# keyDuino_v5_rev1.net
KiCad netlist of a schematic drawn in EAGLE
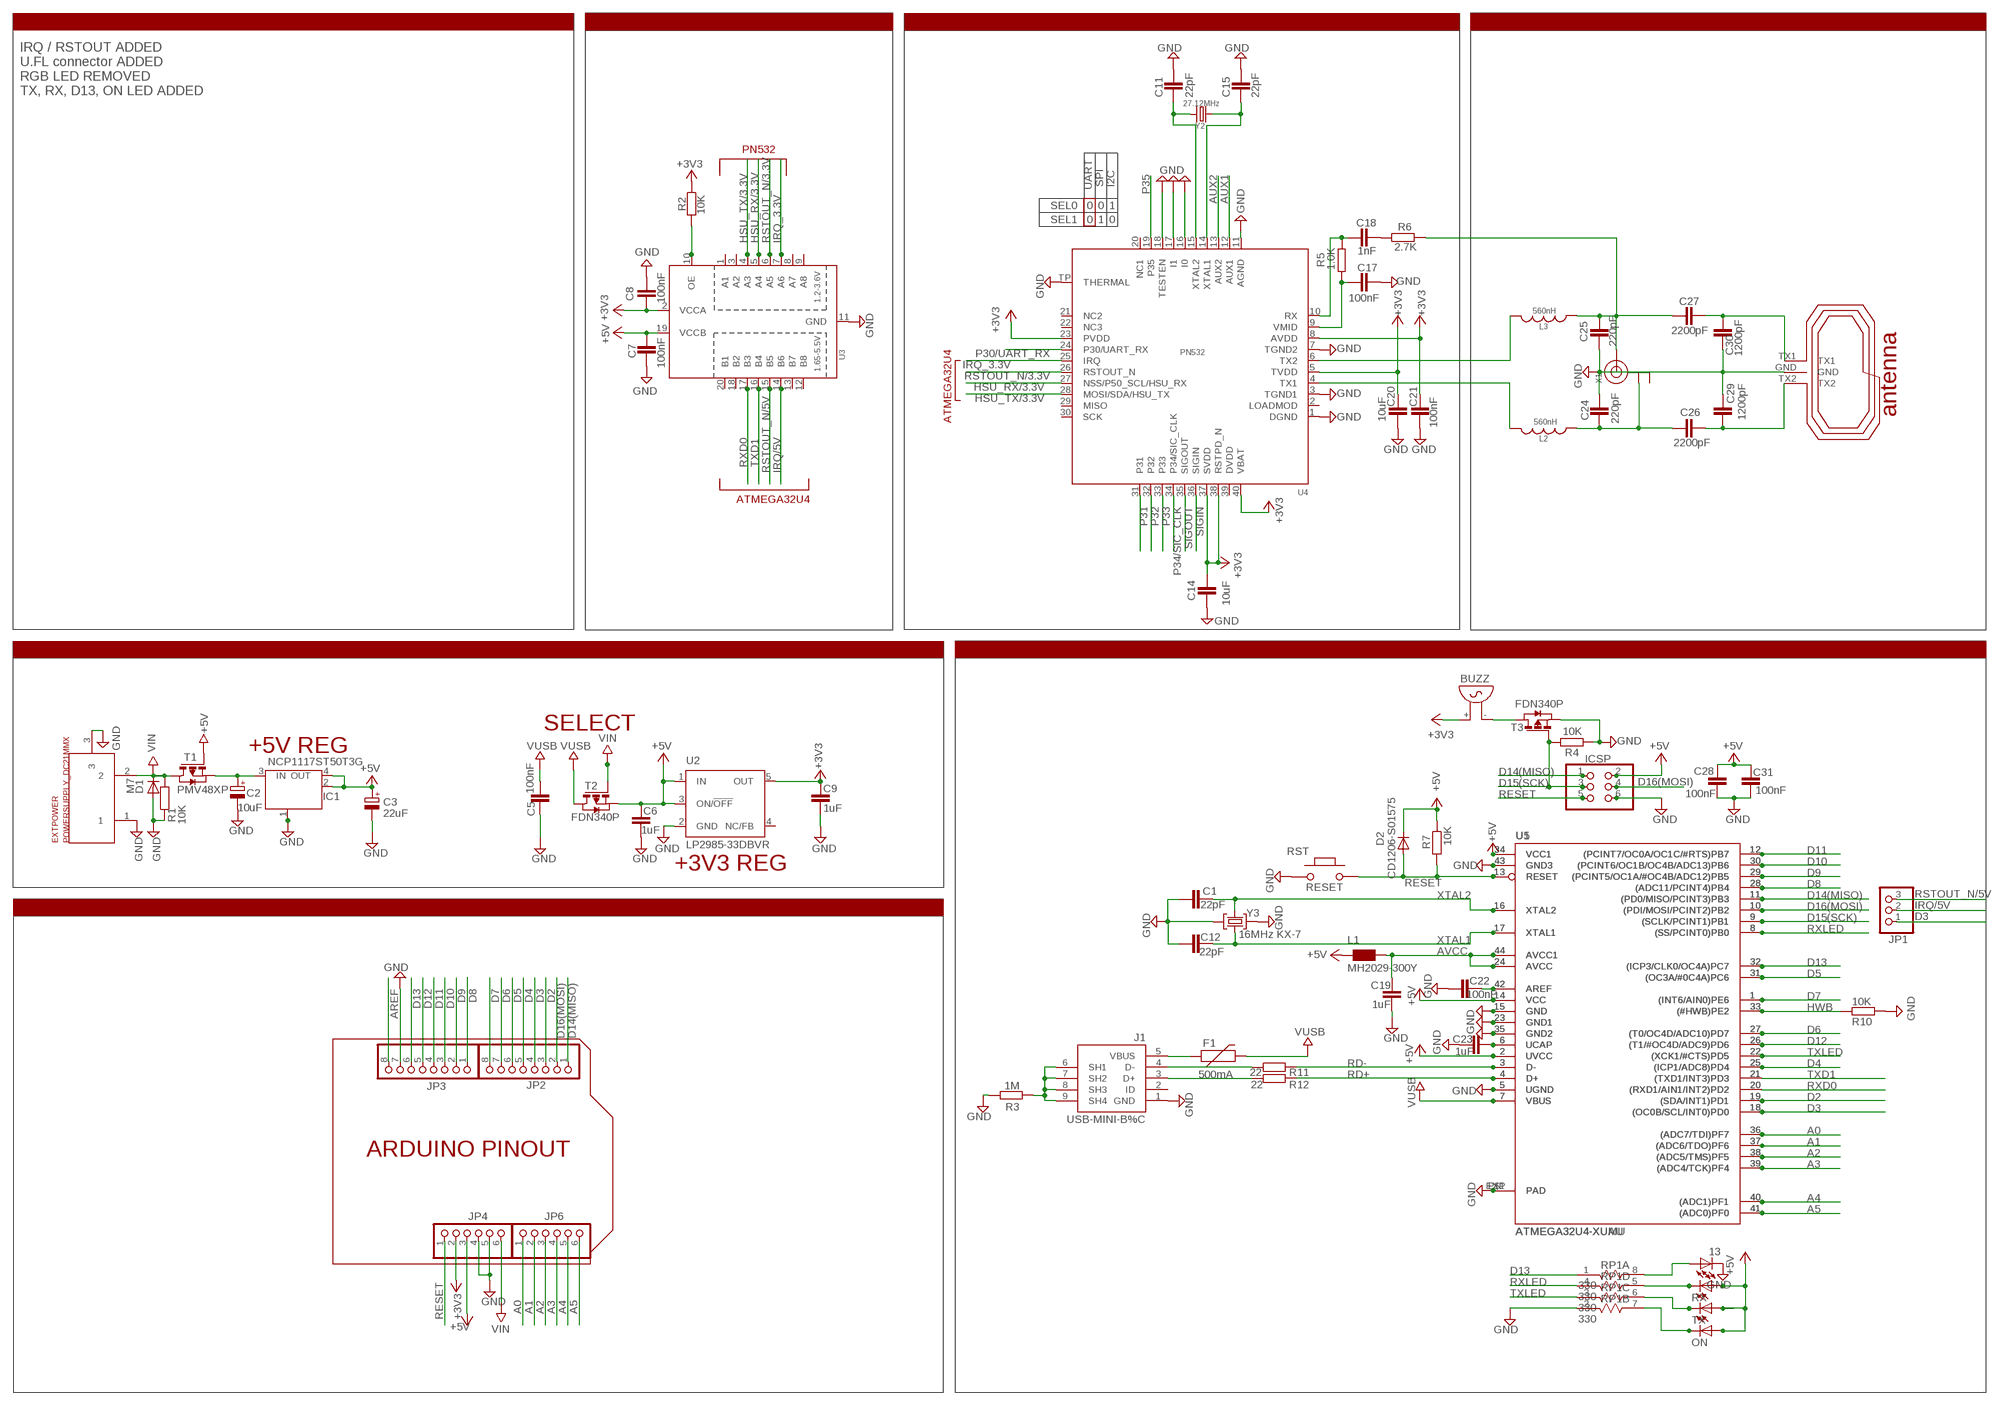
[diagram p0: schematic, sheet 1]

(export (version "E")
  (design (tool "Eeschema 10.0.6"))
  (components
    (comp (ref "13")
      (value "LEDCHIPLED_0603")
      (footprint "eagle-import:CHIPLED_0603")
      (libsource (lib "eagle-import") (part "LEDCHIPLED_0603"))
    )
    (comp (ref "BUZZ")
      (value "F/QMX")
      (footprint "eagle-import:F_QMX")
      (libsource (lib "eagle-import") (part "F/QMX"))
    )
    (comp (ref "C1")
      (value "22pF")
      (footprint "eagle-import:0603-CAP")
      (libsource (lib "eagle-import") (part "CAP0603-CAP"))
    )
    (comp (ref "C2")
      (value "10uF")
      (footprint "eagle-import:SMC_B")
      (libsource (lib "eagle-import") (part "CPOL-EUSMCB"))
    )
    (comp (ref "C3")
      (value "22uF")
      (footprint "eagle-import:SMC_B")
      (libsource (lib "eagle-import") (part "CPOL-EUSMCB"))
    )
    (comp (ref "C5")
      (value "100nF")
      (footprint "eagle-import:C0603")
      (libsource (lib "eagle-import") (part "resistor_C-EUC0603"))
    )
    (comp (ref "C6")
      (value "1uF")
      (footprint "eagle-import:C0603")
      (libsource (lib "eagle-import") (part "C-EUC0603"))
    )
    (comp (ref "C7")
      (value "100nF")
      (footprint "eagle-import:C0603")
      (libsource (lib "eagle-import") (part "C-EUC0603"))
    )
    (comp (ref "C8")
      (value "100nF")
      (footprint "eagle-import:C0603")
      (libsource (lib "eagle-import") (part "C-EUC0603"))
    )
    (comp (ref "C9")
      (value "1uF")
      (footprint "eagle-import:C0603")
      (libsource (lib "eagle-import") (part "C-EUC0603"))
    )
    (comp (ref "C11")
      (value "22pF")
      (footprint "eagle-import:0603-CAP")
      (libsource (lib "eagle-import") (part "CAP0603-CAP"))
    )
    (comp (ref "C12")
      (value "22pF")
      (footprint "eagle-import:0603-CAP")
      (libsource (lib "eagle-import") (part "CAP0603-CAP"))
    )
    (comp (ref "C14")
      (value "10uF")
      (footprint "eagle-import:C0805")
      (libsource (lib "eagle-import") (part "C-EUC0805"))
    )
    (comp (ref "C15")
      (value "22pF")
      (footprint "eagle-import:0603-CAP")
      (libsource (lib "eagle-import") (part "CAP0603-CAP"))
    )
    (comp (ref "C17")
      (value "100nF")
      (footprint "eagle-import:C0603")
      (libsource (lib "eagle-import") (part "C-EUC0603"))
    )
    (comp (ref "C18")
      (value "1nF")
      (footprint "eagle-import:C0603")
      (libsource (lib "eagle-import") (part "C-EUC0603"))
    )
    (comp (ref "C19")
      (value "1uF")
      (footprint "eagle-import:C0603")
      (libsource (lib "eagle-import") (part "resistor_C-EUC0603"))
    )
    (comp (ref "C20")
      (value "10uF")
      (footprint "eagle-import:C0805")
      (libsource (lib "eagle-import") (part "C-EUC0805"))
    )
    (comp (ref "C21")
      (value "100nF")
      (footprint "eagle-import:C0805")
      (libsource (lib "eagle-import") (part "C-EUC0805"))
    )
    (comp (ref "C22")
      (value "100nF")
      (footprint "eagle-import:C0603")
      (libsource (lib "eagle-import") (part "resistor_C-EUC0603"))
    )
    (comp (ref "C23")
      (value "1uF")
      (footprint "eagle-import:C0603")
      (libsource (lib "eagle-import") (part "resistor_C-EUC0603"))
    )
    (comp (ref "C24")
      (value "220pF")
      (footprint "eagle-import:C0603")
      (libsource (lib "eagle-import") (part "C-EUC0603"))
    )
    (comp (ref "C25")
      (value "220pF")
      (footprint "eagle-import:C0603")
      (libsource (lib "eagle-import") (part "C-EUC0603"))
    )
    (comp (ref "C26")
      (value "2200pF")
      (footprint "eagle-import:C0603")
      (libsource (lib "eagle-import") (part "C-EUC0603"))
    )
    (comp (ref "C27")
      (value "2200pF")
      (footprint "eagle-import:C0603")
      (libsource (lib "eagle-import") (part "C-EUC0603"))
    )
    (comp (ref "C28")
      (value "100nF")
      (footprint "eagle-import:C0603")
      (libsource (lib "eagle-import") (part "resistor_C-EUC0603"))
    )
    (comp (ref "C29")
      (value "1200pF")
      (footprint "eagle-import:C0603")
      (libsource (lib "eagle-import") (part "C-EUC0603"))
    )
    (comp (ref "C30")
      (value "1200pF")
      (footprint "eagle-import:C0603")
      (libsource (lib "eagle-import") (part "C-EUC0603"))
    )
    (comp (ref "C31")
      (value "100nF")
      (footprint "eagle-import:C0603")
      (libsource (lib "eagle-import") (part "resistor_C-EUC0603"))
    )
    (comp (ref "D1")
      (value "M7")
      (footprint "eagle-import:SMB")
      (libsource (lib "eagle-import") (part "DIODE-SMB"))
    )
    (comp (ref "D2")
      (value "CD1206-S01575")
      (footprint "eagle-import:MINIMELF")
      (libsource (lib "eagle-import") (part "DIODE-MINIMELF"))
    )
    (comp (ref "EXTPOWER")
      (value "POWERSUPPLY_DC21MMX")
      (footprint "eagle-import:POWERSUPPLY_DC-21MM")
      (libsource (lib "eagle-import") (part "POWERSUPPLY_DC21MMX"))
    )
    (comp (ref "F1")
      (value "500mA")
      (footprint "eagle-import:PTC-1206")
      (libsource (lib "eagle-import") (part "PTCSMD"))
    )
    (comp (ref "IC1")
      (value "NCP1117ST50T3G")
      (footprint "eagle-import:SOT223")
      (libsource (lib "eagle-import") (part "MC33269ST-3.3T3"))
    )
    (comp (ref "ICSP")
      (value "ICSP")
      (footprint "eagle-import:2X03")
      (libsource (lib "eagle-import") (part "PINHD-2X3"))
    )
    (comp (ref "J1")
      (value "USB-MINI-B%C")
      (footprint "eagle-import:USB-MINI-B_2")
      (libsource (lib "eagle-import") (part "USB-MINI-B%C"))
    )
    (comp (ref "JP1")
      (value "PINHD-1X3")
      (footprint "eagle-import:1X03")
      (libsource (lib "eagle-import") (part "PINHD-1X3"))
    )
    (comp (ref "JP2")
      (value "PINHD-1X8CLEANBIG")
      (footprint "eagle-import:1X08-CLEANBIG")
      (libsource (lib "eagle-import") (part "PINHD-1X8CLEANBIG"))
    )
    (comp (ref "JP3")
      (value "PINHD-1X8CLEANBIG")
      (footprint "eagle-import:1X08-CLEANBIG")
      (libsource (lib "eagle-import") (part "PINHD-1X8CLEANBIG"))
    )
    (comp (ref "JP4")
      (value "PINHD-1X6CB")
      (footprint "eagle-import:1X06-CLEANBIG")
      (libsource (lib "eagle-import") (part "PINHD-1X6CB"))
    )
    (comp (ref "JP6")
      (value "PINHD-1X6CB")
      (footprint "eagle-import:1X06-CLEANBIG")
      (libsource (lib "eagle-import") (part "PINHD-1X6CB"))
    )
    (comp (ref "L1")
      (value "MH2029-300Y")
      (footprint "eagle-import:0805")
      (libsource (lib "eagle-import") (part "WE-CBF_0805"))
    )
    (comp (ref "L2")
      (value "560nH")
      (footprint "eagle-import:0805@1")
      (libsource (lib "eagle-import") (part "INDUCTOR0805"))
    )
    (comp (ref "L3")
      (value "560nH")
      (footprint "eagle-import:0805@1")
      (libsource (lib "eagle-import") (part "INDUCTOR0805"))
    )
    (comp (ref "ON")
      (value "LEDCHIPLED_0603")
      (footprint "eagle-import:CHIPLED_0603")
      (libsource (lib "eagle-import") (part "LEDCHIPLED_0603"))
    )
    (comp (ref "R1")
      (value "10K")
      (footprint "eagle-import:R0603")
      (libsource (lib "eagle-import") (part "resistor_R-EU_R0603"))
    )
    (comp (ref "R2")
      (value "10K")
      (footprint "eagle-import:R0603")
      (libsource (lib "eagle-import") (part "R-EU_R0603"))
    )
    (comp (ref "R3")
      (value "1M")
      (footprint "eagle-import:R0805")
      (libsource (lib "eagle-import") (part "R-EU_R0805"))
    )
    (comp (ref "R4")
      (value "10K")
      (footprint "eagle-import:R0603")
      (libsource (lib "eagle-import") (part "R-EU_R0603"))
    )
    (comp (ref "R5")
      (value "1.0K")
      (footprint "eagle-import:R0603")
      (libsource (lib "eagle-import") (part "R-EU_R0603"))
    )
    (comp (ref "R6")
      (value "2.7K")
      (footprint "eagle-import:R0603")
      (libsource (lib "eagle-import") (part "R-EU_R0603"))
    )
    (comp (ref "R7")
      (value "10K")
      (footprint "eagle-import:R0603")
      (libsource (lib "eagle-import") (part "R-EU_R0603"))
    )
    (comp (ref "R10")
      (value "10K")
      (footprint "eagle-import:R0603")
      (libsource (lib "eagle-import") (part "R-EU_R0603"))
    )
    (comp (ref "R11")
      (value "22")
      (footprint "eagle-import:R0603")
      (libsource (lib "eagle-import") (part "R-EU_R0603"))
    )
    (comp (ref "R12")
      (value "22")
      (footprint "eagle-import:R0603")
      (libsource (lib "eagle-import") (part "R-EU_R0603"))
    )
    (comp (ref "RP1")
      (value "330")
      (footprint "eagle-import:RES4NT")
      (libsource (lib "eagle-import") (part "RES4NT"))
    )
    (comp (ref "RST")
      (value "RESET")
      (footprint "eagle-import:157SW")
      (libsource (lib "eagle-import") (part "PB157"))
    )
    (comp (ref "RX")
      (value "LEDCHIPLED_0603")
      (footprint "eagle-import:CHIPLED_0603")
      (libsource (lib "eagle-import") (part "LEDCHIPLED_0603"))
    )
    (comp (ref "T1")
      (value "PMV48XP")
      (footprint "eagle-import:SOT-23")
      (libsource (lib "eagle-import") (part "PMOSSOT23"))
    )
    (comp (ref "T2")
      (value "FDN340P")
      (footprint "eagle-import:SOT-23")
      (libsource (lib "eagle-import") (part "PMOSSOT23"))
    )
    (comp (ref "T3")
      (value "FDN340P")
      (footprint "eagle-import:SOT-23")
      (libsource (lib "eagle-import") (part "PMOSSOT23"))
    )
    (comp (ref "TX")
      (value "LEDCHIPLED_0603")
      (footprint "eagle-import:CHIPLED_0603")
      (libsource (lib "eagle-import") (part "LEDCHIPLED_0603"))
    )
    (comp (ref "U$1")
      (value "ANT_V3")
      (footprint "eagle-import:ANT_13.56_P4")
      (libsource (lib "eagle-import") (part "ANT_V3"))
    )
    (comp (ref "U1")
      (value "ATMEGA32U4-XUAU")
      (footprint "eagle-import:TQFP44-PAD")
      (libsource (lib "eagle-import") (part "ATMEGA32U4-XUAU"))
    )
    (comp (ref "U2")
      (value "LP2985-33DBVR")
      (footprint "eagle-import:SOT23-DBV")
      (libsource (lib "eagle-import") (part "LP2985-XXDBVR33"))
    )
    (comp (ref "U3")
      (value "TXB0108PWR")
      (footprint "eagle-import:TSSOP20")
      (libsource (lib "eagle-import") (part "TXB0108PWR"))
    )
    (comp (ref "U4")
      (value "PN532")
      (footprint "eagle-import:HVQFN40-6X6")
      (libsource (lib "eagle-import") (part "PN532"))
    )
    (comp (ref "U5")
      (value "ATMEGA32U4-XUMU")
      (footprint "eagle-import:QFN44ML7X7")
      (libsource (lib "eagle-import") (part "ATMEGA32U4-XUMU"))
    )
    (comp (ref "X1")
      (value "ANTENNA_U.FL")
      (footprint "eagle-import:U.FL")
      (libsource (lib "eagle-import") (part "ANTENNA_U.FL"))
    )
    (comp (ref "Y2")
      (value "27.12MHz")
      (footprint "eagle-import:CRYSTAL_3.2X2.5")
      (libsource (lib "eagle-import") (part "CRYSTALTHIN"))
    )
    (comp (ref "Y3")
      (value "16MHz KX-7")
      (footprint "eagle-import:CRYSTAL-3.2-2.5")
      (libsource (lib "eagle-import") (part "CRYSTAL-3.2-2.5"))
    )
  )
  (nets
    (net (code "1") (name "+3V3") (class "Default")
      (node (ref "BUZZ") (pin "+") (pinfunction "2_+") (pintype "passive"))
      (node (ref "C14") (pin "2") (pinfunction "2_2") (pintype "passive"))
      (node (ref "C20") (pin "2") (pinfunction "2_2") (pintype "passive"))
      (node (ref "C21") (pin "2") (pinfunction "2_2") (pintype "passive"))
      (node (ref "C8") (pin "1") (pinfunction "1_1") (pintype "passive"))
      (node (ref "C9") (pin "2") (pinfunction "2_2") (pintype "passive"))
      (node (ref "JP4") (pin "2") (pinfunction "2_2") (pintype "passive"))
      (node (ref "R2") (pin "1") (pinfunction "1_1") (pintype "passive"))
      (node (ref "U2") (pin "5") (pinfunction "OUT_5") (pintype "passive"))
      (node (ref "U3") (pin "2") (pinfunction "VCCA_2") (pintype "bidirectional"))
      (node (ref "U4") (pin "23") (pinfunction "PVDD_23") (pintype "bidirectional"))
      (node (ref "U4") (pin "37") (pinfunction "SVDD_37") (pintype "bidirectional"))
      (node (ref "U4") (pin "38") (pinfunction "RSTPD_N_38") (pintype "bidirectional"))
      (node (ref "U4") (pin "40") (pinfunction "VBAT_40") (pintype "bidirectional"))
      (node (ref "U4") (pin "5") (pinfunction "TVDD_5") (pintype "bidirectional"))
      (node (ref "U4") (pin "8") (pinfunction "AVDD_8") (pintype "bidirectional"))
    )
    (net (code "2") (name "+5V") (class "Default")
      (node (ref "C28") (pin "1") (pinfunction "1_1") (pintype "passive"))
      (node (ref "C3") (pin "+") (pinfunction "+_+") (pintype "passive"))
      (node (ref "C31") (pin "1") (pinfunction "1_1") (pintype "passive"))
      (node (ref "C6") (pin "2") (pinfunction "2_2") (pintype "passive"))
      (node (ref "C7") (pin "2") (pinfunction "2_2") (pintype "passive"))
      (node (ref "D2") (pin "C") (pinfunction "C_C") (pintype "passive"))
      (node (ref "IC1") (pin "2") (pinfunction "OUT_2") (pintype "passive"))
      (node (ref "IC1") (pin "4") (pinfunction "OUT_4") (pintype "passive"))
      (node (ref "ICSP") (pin "2") (pinfunction "2_2") (pintype "passive"))
      (node (ref "JP4") (pin "3") (pinfunction "3_3") (pintype "passive"))
      (node (ref "L1") (pin "1") (pinfunction "1_1") (pintype "passive"))
      (node (ref "ON") (pin "A") (pinfunction "A_A") (pintype "passive"))
      (node (ref "R7") (pin "1") (pinfunction "1_1") (pintype "passive"))
      (node (ref "RX") (pin "A") (pinfunction "A_A") (pintype "passive"))
      (node (ref "T1") (pin "3") (pinfunction "G_3") (pintype "passive"))
      (node (ref "T2") (pin "2") (pinfunction "S_2") (pintype "passive"))
      (node (ref "TX") (pin "A") (pinfunction "A_A") (pintype "passive"))
      (node (ref "U1") (pin "14") (pinfunction "VCC_14") (pintype "power_in"))
      (node (ref "U1") (pin "2") (pinfunction "UVCC_2") (pintype "power_in"))
      (node (ref "U1") (pin "34") (pinfunction "VCC1_34") (pintype "power_in"))
      (node (ref "U2") (pin "1") (pinfunction "IN_1") (pintype "input"))
      (node (ref "U2") (pin "3") (pinfunction "ON/~{OFF}_3") (pintype "input"))
      (node (ref "U3") (pin "19") (pinfunction "VCCB_19") (pintype "bidirectional"))
      (node (ref "U5") (pin "14") (pinfunction "VCC_14") (pintype "power_in"))
      (node (ref "U5") (pin "2") (pinfunction "UVCC_2") (pintype "power_in"))
      (node (ref "U5") (pin "34") (pinfunction "VCC1_34") (pintype "power_in"))
    )
    (net (code "3") (name "/A0") (class "Default")
      (node (ref "JP6") (pin "1") (pinfunction "1_1") (pintype "passive"))
      (node (ref "U1") (pin "36") (pinfunction "(ADC7/TDI)PF7_36") (pintype "bidirectional"))
      (node (ref "U5") (pin "36") (pinfunction "(ADC7/TDI)PF7_36") (pintype "bidirectional"))
    )
    (net (code "4") (name "/A1") (class "Default")
      (node (ref "JP6") (pin "2") (pinfunction "2_2") (pintype "passive"))
      (node (ref "U1") (pin "37") (pinfunction "(ADC6/TDO)PF6_37") (pintype "bidirectional"))
      (node (ref "U5") (pin "37") (pinfunction "(ADC6/TDO)PF6_37") (pintype "bidirectional"))
    )
    (net (code "5") (name "/A2") (class "Default")
      (node (ref "JP6") (pin "3") (pinfunction "3_3") (pintype "passive"))
      (node (ref "U1") (pin "38") (pinfunction "(ADC5/TMS)PF5_38") (pintype "bidirectional"))
      (node (ref "U5") (pin "38") (pinfunction "(ADC5/TMS)PF5_38") (pintype "bidirectional"))
    )
    (net (code "6") (name "/A3") (class "Default")
      (node (ref "JP6") (pin "4") (pinfunction "4_4") (pintype "passive"))
      (node (ref "U1") (pin "39") (pinfunction "(ADC4/TCK)PF4_39") (pintype "bidirectional"))
      (node (ref "U5") (pin "39") (pinfunction "(ADC4/TCK)PF4_39") (pintype "bidirectional"))
    )
    (net (code "7") (name "/A4") (class "Default")
      (node (ref "JP6") (pin "5") (pinfunction "5_5") (pintype "passive"))
      (node (ref "U1") (pin "40") (pinfunction "(ADC1)PF1_40") (pintype "bidirectional"))
      (node (ref "U5") (pin "40") (pinfunction "(ADC1)PF1_40") (pintype "bidirectional"))
    )
    (net (code "8") (name "/A5") (class "Default")
      (node (ref "JP6") (pin "6") (pinfunction "6_6") (pintype "passive"))
      (node (ref "U1") (pin "41") (pinfunction "(ADC0)PF0_41") (pintype "bidirectional"))
      (node (ref "U5") (pin "41") (pinfunction "(ADC0)PF0_41") (pintype "bidirectional"))
    )
    (net (code "9") (name "/AREF") (class "Default")
      (node (ref "C22") (pin "1") (pinfunction "1_1") (pintype "passive"))
      (node (ref "JP3") (pin "8") (pinfunction "8_8") (pintype "passive"))
      (node (ref "U1") (pin "42") (pinfunction "AREF_42") (pintype "power_in"))
      (node (ref "U5") (pin "42") (pinfunction "AREF_42") (pintype "power_in"))
    )
    (net (code "10") (name "/AUX1") (class "Default")
      (node (ref "U4") (pin "12") (pinfunction "AUX1_12") (pintype "bidirectional"))
    )
    (net (code "11") (name "/AUX2") (class "Default")
      (node (ref "U4") (pin "13") (pinfunction "AUX2_13") (pintype "bidirectional"))
    )
    (net (code "12") (name "/AVCC") (class "Default")
      (node (ref "C19") (pin "1") (pinfunction "1_1") (pintype "passive"))
      (node (ref "L1") (pin "2") (pinfunction "2_2") (pintype "passive"))
      (node (ref "U1") (pin "24") (pinfunction "AVCC_24") (pintype "power_in"))
      (node (ref "U1") (pin "44") (pinfunction "AVCC1_44") (pintype "power_in"))
      (node (ref "U5") (pin "24") (pinfunction "AVCC_24") (pintype "power_in"))
      (node (ref "U5") (pin "44") (pinfunction "AVCC1_44") (pintype "power_in"))
    )
    (net (code "13") (name "/D2") (class "Default")
      (node (ref "JP2") (pin "3") (pinfunction "3_3") (pintype "passive"))
      (node (ref "U1") (pin "19") (pinfunction "(SDA/INT1)PD1_19") (pintype "bidirectional"))
      (node (ref "U5") (pin "19") (pinfunction "(SDA/INT1)PD1_19") (pintype "bidirectional"))
    )
    (net (code "14") (name "/D3") (class "Default")
      (node (ref "JP1") (pin "1") (pinfunction "1_1") (pintype "passive"))
      (node (ref "JP2") (pin "4") (pinfunction "4_4") (pintype "passive"))
      (node (ref "U1") (pin "18") (pinfunction "(OC0B/SCL/INT0)PD0_18") (pintype "bidirectional"))
      (node (ref "U5") (pin "18") (pinfunction "(OC0B/SCL/INT0)PD0_18") (pintype "bidirectional"))
    )
    (net (code "15") (name "/D4") (class "Default")
      (node (ref "JP2") (pin "5") (pinfunction "5_5") (pintype "passive"))
      (node (ref "U1") (pin "25") (pinfunction "(ICP1/ADC8)PD4_25") (pintype "bidirectional"))
      (node (ref "U5") (pin "25") (pinfunction "(ICP1/ADC8)PD4_25") (pintype "bidirectional"))
    )
    (net (code "16") (name "/D5") (class "Default")
      (node (ref "JP2") (pin "6") (pinfunction "6_6") (pintype "passive"))
      (node (ref "U1") (pin "31") (pinfunction "(OC3A/#0C4A)PC6_31") (pintype "bidirectional"))
      (node (ref "U5") (pin "31") (pinfunction "(OC3A/#0C4A)PC6_31") (pintype "bidirectional"))
    )
    (net (code "17") (name "/D6") (class "Default")
      (node (ref "JP2") (pin "7") (pinfunction "7_7") (pintype "passive"))
      (node (ref "U1") (pin "27") (pinfunction "(T0/OC4D/ADC10)PD7_27") (pintype "bidirectional"))
      (node (ref "U5") (pin "27") (pinfunction "(T0/OC4D/ADC10)PD7_27") (pintype "bidirectional"))
    )
    (net (code "18") (name "/D7") (class "Default")
      (node (ref "JP2") (pin "8") (pinfunction "8_8") (pintype "passive"))
      (node (ref "U1") (pin "1") (pinfunction "(INT6/AIN0)PE6_1") (pintype "bidirectional"))
      (node (ref "U5") (pin "1") (pinfunction "(INT6/AIN0)PE6_1") (pintype "bidirectional"))
    )
    (net (code "19") (name "/D8") (class "Default")
      (node (ref "JP3") (pin "1") (pinfunction "1_1") (pintype "passive"))
      (node (ref "U1") (pin "28") (pinfunction "(ADC11/PCINT4)PB4_28") (pintype "bidirectional"))
      (node (ref "U5") (pin "28") (pinfunction "(ADC11/PCINT4)PB4_28") (pintype "bidirectional"))
    )
    (net (code "20") (name "/D9") (class "Default")
      (node (ref "JP3") (pin "2") (pinfunction "2_2") (pintype "passive"))
      (node (ref "U1") (pin "29") (pinfunction "(PCINT5/OC1A/#OC4B/ADC12)PB5_29") (pintype "bidirectional"))
      (node (ref "U5") (pin "29") (pinfunction "(PCINT5/OC1A/#OC4B/ADC12)PB5_29") (pintype "bidirectional"))
    )
    (net (code "21") (name "/D10") (class "Default")
      (node (ref "JP3") (pin "3") (pinfunction "3_3") (pintype "passive"))
      (node (ref "U1") (pin "30") (pinfunction "(PCINT6/OC1B/OC4B/ADC13)PB6_30") (pintype "bidirectional"))
      (node (ref "U5") (pin "30") (pinfunction "(PCINT6/OC1B/OC4B/ADC13)PB6_30") (pintype "bidirectional"))
    )
    (net (code "22") (name "/D11") (class "Default")
      (node (ref "JP3") (pin "4") (pinfunction "4_4") (pintype "passive"))
      (node (ref "U1") (pin "12") (pinfunction "(PCINT7/OC0A/OC1C/#RTS)PB7_12") (pintype "bidirectional"))
      (node (ref "U5") (pin "12") (pinfunction "(PCINT7/OC0A/OC1C/#RTS)PB7_12") (pintype "bidirectional"))
    )
    (net (code "23") (name "/D12") (class "Default")
      (node (ref "JP3") (pin "5") (pinfunction "5_5") (pintype "passive"))
      (node (ref "U1") (pin "26") (pinfunction "(T1/#OC4D/ADC9)PD6_26") (pintype "bidirectional"))
      (node (ref "U5") (pin "26") (pinfunction "(T1/#OC4D/ADC9)PD6_26") (pintype "bidirectional"))
    )
    (net (code "24") (name "/D13") (class "Default")
      (node (ref "JP3") (pin "6") (pinfunction "6_6") (pintype "passive"))
      (node (ref "RP1") (pin "1") (pinfunction "1_1") (pintype "passive"))
      (node (ref "U1") (pin "32") (pinfunction "(ICP3/CLK0/OC4A)PC7_32") (pintype "bidirectional"))
      (node (ref "U5") (pin "32") (pinfunction "(ICP3/CLK0/OC4A)PC7_32") (pintype "bidirectional"))
    )
    (net (code "25") (name "/D14(MISO)") (class "Default")
      (node (ref "ICSP") (pin "1") (pinfunction "1_1") (pintype "passive"))
      (node (ref "JP2") (pin "1") (pinfunction "1_1") (pintype "passive"))
      (node (ref "U1") (pin "11") (pinfunction "(PD0/MISO/PCINT3)PB3_11") (pintype "bidirectional"))
      (node (ref "U5") (pin "11") (pinfunction "(PD0/MISO/PCINT3)PB3_11") (pintype "bidirectional"))
    )
    (net (code "26") (name "/D15(SCK)") (class "Default")
      (node (ref "ICSP") (pin "3") (pinfunction "3_3") (pintype "passive"))
      (node (ref "R4") (pin "1") (pinfunction "1_1") (pintype "passive"))
      (node (ref "T3") (pin "3") (pinfunction "G_3") (pintype "passive"))
      (node (ref "U1") (pin "9") (pinfunction "(SCLK/PCINT1)PB1_9") (pintype "bidirectional"))
      (node (ref "U5") (pin "9") (pinfunction "(SCLK/PCINT1)PB1_9") (pintype "bidirectional"))
    )
    (net (code "27") (name "/D16(MOSI)") (class "Default")
      (node (ref "ICSP") (pin "4") (pinfunction "4_4") (pintype "passive"))
      (node (ref "JP2") (pin "2") (pinfunction "2_2") (pintype "passive"))
      (node (ref "U1") (pin "10") (pinfunction "(PDI/MOSI/PCINT2)PB2_10") (pintype "bidirectional"))
      (node (ref "U5") (pin "10") (pinfunction "(PDI/MOSI/PCINT2)PB2_10") (pintype "bidirectional"))
    )
    (net (code "28") (name "/HSU_RX{slash}3.3V") (class "Default")
      (node (ref "U3") (pin "5") (pinfunction "A4_5") (pintype "bidirectional"))
      (node (ref "U4") (pin "27") (pinfunction "NSS/P50_SCL/HSU_RX_27") (pintype "bidirectional"))
    )
    (net (code "29") (name "/HSU_TX{slash}3.3V") (class "Default")
      (node (ref "U3") (pin "4") (pinfunction "A3_4") (pintype "bidirectional"))
      (node (ref "U4") (pin "28") (pinfunction "MOSI/SDA/HSU_TX_28") (pintype "bidirectional"))
    )
    (net (code "30") (name "/HWB") (class "Default")
      (node (ref "R10") (pin "1") (pinfunction "1_1") (pintype "passive"))
      (node (ref "U1") (pin "33") (pinfunction "(#HWB)PE2_33") (pintype "bidirectional"))
      (node (ref "U5") (pin "33") (pinfunction "(#HWB)PE2_33") (pintype "bidirectional"))
    )
    (net (code "31") (name "/IRQ_3.3V") (class "Default")
      (node (ref "U3") (pin "7") (pinfunction "A6_7") (pintype "bidirectional"))
      (node (ref "U4") (pin "25") (pinfunction "IRQ_25") (pintype "bidirectional"))
    )
    (net (code "32") (name "/IRQ{slash}5V") (class "Default")
      (node (ref "JP1") (pin "2") (pinfunction "2_2") (pintype "passive"))
      (node (ref "U3") (pin "14") (pinfunction "B6_14") (pintype "bidirectional"))
    )
    (net (code "33") (name "/P30{slash}UART_RX") (class "Default")
      (node (ref "U4") (pin "24") (pinfunction "P30/UART_RX_24") (pintype "bidirectional"))
    )
    (net (code "34") (name "/P31") (class "Default")
      (node (ref "U4") (pin "31") (pinfunction "P31_31") (pintype "bidirectional"))
    )
    (net (code "35") (name "/P32") (class "Default")
      (node (ref "U4") (pin "32") (pinfunction "P32_32") (pintype "bidirectional"))
    )
    (net (code "36") (name "/P33") (class "Default")
      (node (ref "U4") (pin "33") (pinfunction "P33_33") (pintype "bidirectional"))
    )
    (net (code "37") (name "/P34{slash}SIC_CLK") (class "Default")
      (node (ref "U4") (pin "34") (pinfunction "P34/SIC_CLK_34") (pintype "bidirectional"))
    )
    (net (code "38") (name "/P35") (class "Default")
      (node (ref "U4") (pin "19") (pinfunction "P35_19") (pintype "bidirectional"))
    )
    (net (code "39") (name "/RD+") (class "Default")
      (node (ref "R12") (pin "2") (pinfunction "2_2") (pintype "passive"))
      (node (ref "U1") (pin "4") (pinfunction "D+_4") (pintype "bidirectional"))
      (node (ref "U5") (pin "4") (pinfunction "D+_4") (pintype "bidirectional"))
    )
    (net (code "40") (name "/RD-") (class "Default")
      (node (ref "R11") (pin "2") (pinfunction "2_2") (pintype "passive"))
      (node (ref "U1") (pin "3") (pinfunction "D-_3") (pintype "bidirectional"))
      (node (ref "U5") (pin "3") (pinfunction "D-_3") (pintype "bidirectional"))
    )
    (net (code "41") (name "/RESET") (class "Default")
      (node (ref "D2") (pin "A") (pinfunction "A_A") (pintype "passive"))
      (node (ref "ICSP") (pin "5") (pinfunction "5_5") (pintype "passive"))
      (node (ref "JP4") (pin "1") (pinfunction "1_1") (pintype "passive"))
      (node (ref "R7") (pin "2") (pinfunction "2_2") (pintype "passive"))
      (node (ref "RST") (pin "2") (pinfunction "2_2") (pintype "passive"))
      (node (ref "U1") (pin "13") (pinfunction "RESET_13") (pintype "input"))
      (node (ref "U5") (pin "13") (pinfunction "RESET_13") (pintype "input"))
    )
    (net (code "42") (name "/RSTOUT_N{slash}3.3V") (class "Default")
      (node (ref "U3") (pin "6") (pinfunction "A5_6") (pintype "bidirectional"))
      (node (ref "U4") (pin "26") (pinfunction "RSTOUT_N_26") (pintype "bidirectional"))
    )
    (net (code "43") (name "/RSTOUT_N{slash}5V") (class "Default")
      (node (ref "JP1") (pin "3") (pinfunction "3_3") (pintype "passive"))
      (node (ref "U3") (pin "15") (pinfunction "B5_15") (pintype "bidirectional"))
    )
    (net (code "44") (name "/RXD0") (class "Default")
      (node (ref "U1") (pin "20") (pinfunction "(RXD1/AIN1/INT2)PD2_20") (pintype "bidirectional"))
      (node (ref "U3") (pin "17") (pinfunction "B3_17") (pintype "bidirectional"))
      (node (ref "U5") (pin "20") (pinfunction "(RXD1/AIN1/INT2)PD2_20") (pintype "bidirectional"))
    )
    (net (code "45") (name "/RXLED") (class "Default")
      (node (ref "RP1") (pin "4") (pinfunction "1_4") (pintype "passive"))
      (node (ref "U1") (pin "8") (pinfunction "(SS/PCINT0)PB0_8") (pintype "bidirectional"))
      (node (ref "U5") (pin "8") (pinfunction "(SS/PCINT0)PB0_8") (pintype "bidirectional"))
    )
    (net (code "46") (name "/SIGIN") (class "Default")
      (node (ref "U4") (pin "36") (pinfunction "SIGIN_36") (pintype "bidirectional"))
    )
    (net (code "47") (name "/SIGOUT") (class "Default")
      (node (ref "U4") (pin "35") (pinfunction "SIGOUT_35") (pintype "bidirectional"))
    )
    (net (code "48") (name "/TXD1") (class "Default")
      (node (ref "U1") (pin "21") (pinfunction "(TXD1/INT3)PD3_21") (pintype "bidirectional"))
      (node (ref "U3") (pin "16") (pinfunction "B4_16") (pintype "bidirectional"))
      (node (ref "U5") (pin "21") (pinfunction "(TXD1/INT3)PD3_21") (pintype "bidirectional"))
    )
    (net (code "49") (name "/TXLED") (class "Default")
      (node (ref "RP1") (pin "3") (pinfunction "1_3") (pintype "passive"))
      (node (ref "U1") (pin "22") (pinfunction "(XCK1/#CTS)PD5_22") (pintype "bidirectional"))
      (node (ref "U5") (pin "22") (pinfunction "(XCK1/#CTS)PD5_22") (pintype "bidirectional"))
    )
    (net (code "50") (name "/XTAL1") (class "Default")
      (node (ref "C12") (pin "2") (pinfunction "2_2") (pintype "passive"))
      (node (ref "U1") (pin "17") (pinfunction "XTAL1_17") (pintype "bidirectional"))
      (node (ref "U5") (pin "17") (pinfunction "XTAL1_17") (pintype "bidirectional"))
      (node (ref "Y3") (pin "1") (pinfunction "C1_1") (pintype "passive"))
    )
    (net (code "51") (name "/XTAL2") (class "Default")
      (node (ref "C1") (pin "2") (pinfunction "2_2") (pintype "passive"))
      (node (ref "U1") (pin "16") (pinfunction "XTAL2_16") (pintype "bidirectional"))
      (node (ref "U5") (pin "16") (pinfunction "XTAL2_16") (pintype "bidirectional"))
      (node (ref "Y3") (pin "3") (pinfunction "C2_3") (pintype "passive"))
    )
    (net (code "52") (name "GND") (class "Default")
      (node (ref "13") (pin "C") (pinfunction "C_C") (pintype "passive"))
      (node (ref "C1") (pin "1") (pinfunction "1_1") (pintype "passive"))
      (node (ref "C11") (pin "1") (pinfunction "1_1") (pintype "passive"))
      (node (ref "C12") (pin "1") (pinfunction "1_1") (pintype "passive"))
      (node (ref "C14") (pin "1") (pinfunction "1_1") (pintype "passive"))
      (node (ref "C15") (pin "1") (pinfunction "1_1") (pintype "passive"))
      (node (ref "C17") (pin "1") (pinfunction "1_1") (pintype "passive"))
      (node (ref "C19") (pin "2") (pinfunction "2_2") (pintype "passive"))
      (node (ref "C2") (pin "-") (pinfunction "-_-") (pintype "passive"))
      (node (ref "C20") (pin "1") (pinfunction "1_1") (pintype "passive"))
      (node (ref "C21") (pin "1") (pinfunction "1_1") (pintype "passive"))
      (node (ref "C22") (pin "2") (pinfunction "2_2") (pintype "passive"))
      (node (ref "C23") (pin "2") (pinfunction "2_2") (pintype "passive"))
      (node (ref "C24") (pin "1") (pinfunction "1_1") (pintype "passive"))
      (node (ref "C25") (pin "2") (pinfunction "2_2") (pintype "passive"))
      (node (ref "C28") (pin "2") (pinfunction "2_2") (pintype "passive"))
      (node (ref "C29") (pin "1") (pinfunction "1_1") (pintype "passive"))
      (node (ref "C3") (pin "-") (pinfunction "-_-") (pintype "passive"))
      (node (ref "C30") (pin "2") (pinfunction "2_2") (pintype "passive"))
      (node (ref "C31") (pin "2") (pinfunction "2_2") (pintype "passive"))
      (node (ref "C5") (pin "1") (pinfunction "1_1") (pintype "passive"))
      (node (ref "C6") (pin "1") (pinfunction "1_1") (pintype "passive"))
      (node (ref "C7") (pin "1") (pinfunction "1_1") (pintype "passive"))
      (node (ref "C8") (pin "2") (pinfunction "2_2") (pintype "passive"))
      (node (ref "C9") (pin "1") (pinfunction "1_1") (pintype "passive"))
      (node (ref "D1") (pin "A") (pinfunction "A_A") (pintype "passive"))
      (node (ref "EXTPOWER") (pin "1") (pinfunction "1_1") (pintype "power_in"))
      (node (ref "EXTPOWER") (pin "3") (pinfunction "3_3") (pintype "power_in"))
      (node (ref "IC1") (pin "1") (pinfunction "GND/ADJ_1") (pintype "input"))
      (node (ref "ICSP") (pin "6") (pinfunction "6_6") (pintype "passive"))
      (node (ref "J1") (pin "1") (pinfunction "GND_1") (pintype "passive"))
      (node (ref "JP3") (pin "7") (pinfunction "7_7") (pintype "passive"))
      (node (ref "JP4") (pin "4") (pinfunction "4_4") (pintype "passive"))
      (node (ref "JP4") (pin "5") (pinfunction "5_5") (pintype "passive"))
      (node (ref "R1") (pin "1") (pinfunction "1_1") (pintype "passive"))
      (node (ref "R10") (pin "2") (pinfunction "2_2") (pintype "passive"))
      (node (ref "R3") (pin "1") (pinfunction "1_1") (pintype "passive"))
      (node (ref "R4") (pin "2") (pinfunction "2_2") (pintype "passive"))
      (node (ref "RP1") (pin "2") (pinfunction "1_2") (pintype "passive"))
      (node (ref "RST") (pin "1") (pinfunction "1_1") (pintype "passive"))
      (node (ref "T3") (pin "2") (pinfunction "S_2") (pintype "passive"))
      (node (ref "U$1") (pin "GND") (pinfunction "GND_GND") (pintype "bidirectional"))
      (node (ref "U1") (pin "15") (pinfunction "GND_15") (pintype "power_in"))
      (node (ref "U1") (pin "23") (pinfunction "GND1_23") (pintype "power_in"))
      (node (ref "U1") (pin "35") (pinfunction "GND2_35") (pintype "power_in"))
      (node (ref "U1") (pin "43") (pinfunction "GND3_43") (pintype "power_in"))
      (node (ref "U1") (pin "5") (pinfunction "UGND_5") (pintype "power_in"))
      (node (ref "U1") (pin "P$1") (pinfunction "PAD_P$1") (pintype "power_in"))
      (node (ref "U2") (pin "2") (pinfunction "GND_2") (pintype "power_in"))
      (node (ref "U3") (pin "11") (pinfunction "GND_11") (pintype "bidirectional"))
      (node (ref "U4") (pin "1") (pinfunction "DGND_1") (pintype "bidirectional"))
      (node (ref "U4") (pin "11") (pinfunction "AGND_11") (pintype "bidirectional"))
      (node (ref "U4") (pin "16") (pinfunction "I0_16") (pintype "bidirectional"))
      (node (ref "U4") (pin "17") (pinfunction "I1_17") (pintype "bidirectional"))
      (node (ref "U4") (pin "18") (pinfunction "TESTEN_18") (pintype "bidirectional"))
      (node (ref "U4") (pin "3") (pinfunction "TGND1_3") (pintype "bidirectional"))
      (node (ref "U4") (pin "7") (pinfunction "TGND2_7") (pintype "bidirectional"))
      (node (ref "U4") (pin "TP") (pinfunction "THERMAL_TP") (pintype "bidirectional"))
      (node (ref "U5") (pin "15") (pinfunction "GND_15") (pintype "power_in"))
      (node (ref "U5") (pin "23") (pinfunction "GND1_23") (pintype "power_in"))
      (node (ref "U5") (pin "35") (pinfunction "GND2_35") (pintype "power_in"))
      (node (ref "U5") (pin "43") (pinfunction "GND3_43") (pintype "power_in"))
      (node (ref "U5") (pin "5") (pinfunction "UGND_5") (pintype "power_in"))
      (node (ref "U5") (pin "EXP") (pinfunction "PAD_EXP") (pintype "power_in"))
      (node (ref "Y3") (pin "2") (pinfunction "GND_2") (pintype "passive"))
      (node (ref "Y3") (pin "4") (pinfunction "GND_4") (pintype "passive"))
    )
    (net (code "53") (name "Net-(BUZZ-1)") (class "Default")
      (node (ref "BUZZ") (pin "-") (pinfunction "1_-") (pintype "passive"))
      (node (ref "T3") (pin "1") (pinfunction "D_1") (pintype "passive"))
    )
    (net (code "54") (name "Net-(C18-Pad1)") (class "Default")
      (node (ref "C18") (pin "1") (pinfunction "1_1") (pintype "passive"))
      (node (ref "R6") (pin "1") (pinfunction "1_1") (pintype "passive"))
    )
    (net (code "55") (name "Net-(C24-Pad2)") (class "Default")
      (node (ref "C24") (pin "2") (pinfunction "2_2") (pintype "passive"))
      (node (ref "C26") (pin "1") (pinfunction "1_1") (pintype "passive"))
      (node (ref "L2") (pin "1") (pinfunction "1_1") (pintype "passive"))
      (node (ref "X1") (pin "1") (pinfunction "GND_1") (pintype "passive"))
    )
    (net (code "56") (name "Net-(C26-Pad2)") (class "Default")
      (node (ref "C26") (pin "2") (pinfunction "2_2") (pintype "passive"))
      (node (ref "C29") (pin "2") (pinfunction "2_2") (pintype "passive"))
      (node (ref "U$1") (pin "TX2") (pinfunction "TX2_TX2") (pintype "bidirectional"))
    )
    (net (code "57") (name "Net-(C27-Pad1)") (class "Default")
      (node (ref "C27") (pin "1") (pinfunction "1_1") (pintype "passive"))
      (node (ref "C30") (pin "1") (pinfunction "1_1") (pintype "passive"))
      (node (ref "U$1") (pin "TX1") (pinfunction "TX1_TX1") (pintype "bidirectional"))
    )
    (net (code "58") (name "Net-(IC1-IN)") (class "Default")
      (node (ref "C2") (pin "+") (pinfunction "+_+") (pintype "passive"))
      (node (ref "IC1") (pin "3") (pinfunction "IN_3") (pintype "input"))
      (node (ref "T1") (pin "2") (pinfunction "S_2") (pintype "passive"))
    )
    (net (code "59") (name "Net-(J1-D+)") (class "Default")
      (node (ref "J1") (pin "3") (pinfunction "D+_3") (pintype "bidirectional"))
      (node (ref "R12") (pin "1") (pinfunction "1_1") (pintype "passive"))
    )
    (net (code "60") (name "Net-(J1-D-)") (class "Default")
      (node (ref "J1") (pin "4") (pinfunction "D-_4") (pintype "bidirectional"))
      (node (ref "R11") (pin "1") (pinfunction "1_1") (pintype "passive"))
    )
    (net (code "61") (name "Net-(J1-SH1)") (class "Default")
      (node (ref "J1") (pin "6") (pinfunction "SH1_6") (pintype "passive"))
      (node (ref "J1") (pin "7") (pinfunction "SH2_7") (pintype "passive"))
      (node (ref "J1") (pin "8") (pinfunction "SH3_8") (pintype "passive"))
      (node (ref "J1") (pin "9") (pinfunction "SH4_9") (pintype "passive"))
      (node (ref "R3") (pin "2") (pinfunction "2_2") (pintype "passive"))
    )
    (net (code "62") (name "Net-(J1-VBUS)") (class "Default")
      (node (ref "F1") (pin "1") (pinfunction "1_1") (pintype "bidirectional"))
      (node (ref "J1") (pin "5") (pinfunction "VBUS_5") (pintype "power_in"))
    )
    (net (code "63") (name "Net-(RP1A-2)") (class "Default")
      (node (ref "13") (pin "A") (pinfunction "A_A") (pintype "passive"))
      (node (ref "RP1") (pin "8") (pinfunction "2_8") (pintype "passive"))
    )
    (net (code "64") (name "Net-(RP1B-2)") (class "Default")
      (node (ref "ON") (pin "C") (pinfunction "C_C") (pintype "passive"))
      (node (ref "RP1") (pin "7") (pinfunction "2_7") (pintype "passive"))
    )
    (net (code "65") (name "Net-(RP1C-2)") (class "Default")
      (node (ref "RP1") (pin "6") (pinfunction "2_6") (pintype "passive"))
      (node (ref "TX") (pin "C") (pinfunction "C_C") (pintype "passive"))
    )
    (net (code "66") (name "Net-(RP1D-2)") (class "Default")
      (node (ref "RP1") (pin "5") (pinfunction "2_5") (pintype "passive"))
      (node (ref "RX") (pin "C") (pinfunction "C_C") (pintype "passive"))
    )
    (net (code "67") (name "Net-(U1-UCAP)") (class "Default")
      (node (ref "C23") (pin "1") (pinfunction "1_1") (pintype "passive"))
      (node (ref "U1") (pin "6") (pinfunction "UCAP_6") (pintype "passive"))
      (node (ref "U5") (pin "6") (pinfunction "UCAP_6") (pintype "passive"))
    )
    (net (code "68") (name "Net-(U3-OE)") (class "Default")
      (node (ref "R2") (pin "2") (pinfunction "2_2") (pintype "passive"))
      (node (ref "U3") (pin "10") (pinfunction "OE_10") (pintype "bidirectional"))
    )
    (net (code "69") (name "Net-(U4-RX)") (class "Default")
      (node (ref "C18") (pin "2") (pinfunction "2_2") (pintype "passive"))
      (node (ref "R5") (pin "1") (pinfunction "1_1") (pintype "passive"))
      (node (ref "U4") (pin "10") (pinfunction "RX_10") (pintype "bidirectional"))
    )
    (net (code "70") (name "Net-(U4-TX1)") (class "Default")
      (node (ref "L2") (pin "2") (pinfunction "2_2") (pintype "passive"))
      (node (ref "U4") (pin "4") (pinfunction "TX1_4") (pintype "bidirectional"))
    )
    (net (code "71") (name "Net-(U4-TX2)") (class "Default")
      (node (ref "L3") (pin "2") (pinfunction "2_2") (pintype "passive"))
      (node (ref "U4") (pin "6") (pinfunction "TX2_6") (pintype "bidirectional"))
    )
    (net (code "72") (name "Net-(U4-VMID)") (class "Default")
      (node (ref "C17") (pin "2") (pinfunction "2_2") (pintype "passive"))
      (node (ref "R5") (pin "2") (pinfunction "2_2") (pintype "passive"))
      (node (ref "U4") (pin "9") (pinfunction "VMID_9") (pintype "bidirectional"))
    )
    (net (code "73") (name "Net-(U4-XTAL1)") (class "Default")
      (node (ref "C15") (pin "2") (pinfunction "2_2") (pintype "passive"))
      (node (ref "U4") (pin "14") (pinfunction "XTAL1_14") (pintype "bidirectional"))
      (node (ref "Y2") (pin "1") (pinfunction "1_1") (pintype "passive"))
    )
    (net (code "74") (name "Net-(U4-XTAL2)") (class "Default")
      (node (ref "C11") (pin "2") (pinfunction "2_2") (pintype "passive"))
      (node (ref "U4") (pin "15") (pinfunction "XTAL2_15") (pintype "bidirectional"))
      (node (ref "Y2") (pin "2") (pinfunction "2_2") (pintype "passive"))
    )
    (net (code "75") (name "Net-(X1-SIGNAL)") (class "Default")
      (node (ref "C25") (pin "1") (pinfunction "1_1") (pintype "passive"))
      (node (ref "C27") (pin "2") (pinfunction "2_2") (pintype "passive"))
      (node (ref "L3") (pin "1") (pinfunction "1_1") (pintype "passive"))
      (node (ref "R6") (pin "2") (pinfunction "2_2") (pintype "passive"))
      (node (ref "X1") (pin "3") (pinfunction "SIGNAL_3") (pintype "passive"))
    )
    (net (code "76") (name "VIN") (class "Default")
      (node (ref "D1") (pin "C") (pinfunction "C_C") (pintype "passive"))
      (node (ref "EXTPOWER") (pin "2") (pinfunction "2_2") (pintype "power_in"))
      (node (ref "JP4") (pin "6") (pinfunction "6_6") (pintype "passive"))
      (node (ref "R1") (pin "2") (pinfunction "2_2") (pintype "passive"))
      (node (ref "T1") (pin "1") (pinfunction "D_1") (pintype "passive"))
      (node (ref "T2") (pin "3") (pinfunction "G_3") (pintype "passive"))
    )
    (net (code "77") (name "VUSB") (class "Default")
      (node (ref "C5") (pin "2") (pinfunction "2_2") (pintype "passive"))
      (node (ref "F1") (pin "2") (pinfunction "2_2") (pintype "bidirectional"))
      (node (ref "T2") (pin "1") (pinfunction "D_1") (pintype "passive"))
      (node (ref "U1") (pin "7") (pinfunction "VBUS_7") (pintype "input"))
      (node (ref "U5") (pin "7") (pinfunction "VBUS_7") (pintype "input"))
    )
    (net (code "78") (name "unconnected-(J1-ID-Pad2)") (class "Default")
      (node (ref "J1") (pin "2") (pinfunction "ID_2") (pintype "bidirectional"))
    )
    (net (code "79") (name "unconnected-(U$1-P$1-PadP$10)") (class "Default")
      (node (ref "U$1") (pin "P$10") (pinfunction "P$1_P$10") (pintype "no_connect"))
    )
    (net (code "80") (name "unconnected-(U$1-P$2-PadP$11)") (class "Default")
      (node (ref "U$1") (pin "P$11") (pinfunction "P$2_P$11") (pintype "no_connect"))
    )
    (net (code "81") (name "unconnected-(U$1-P$3-PadP$9)") (class "Default")
      (node (ref "U$1") (pin "P$9") (pinfunction "P$3_P$9") (pintype "no_connect"))
    )
    (net (code "82") (name "unconnected-(U$1-P$4-PadP$8)") (class "Default")
      (node (ref "U$1") (pin "P$8") (pinfunction "P$4_P$8") (pintype "no_connect"))
    )
    (net (code "83") (name "unconnected-(U$1-P$5-PadP$7)") (class "Default")
      (node (ref "U$1") (pin "P$7") (pinfunction "P$5_P$7") (pintype "no_connect"))
    )
    (net (code "84") (name "unconnected-(U$1-P$7-PadP$5)") (class "Default")
      (node (ref "U$1") (pin "P$5") (pinfunction "P$7_P$5") (pintype "no_connect"))
    )
    (net (code "85") (name "unconnected-(U$1-P$8-PadP$4)") (class "Default")
      (node (ref "U$1") (pin "P$4") (pinfunction "P$8_P$4") (pintype "no_connect"))
    )
    (net (code "86") (name "unconnected-(U$1-PadP$6)") (class "Default")
      (node (ref "U$1") (pin "P$6") (pinfunction "P$6_P$6") (pintype "no_connect"))
    )
    (net (code "87") (name "unconnected-(U2-NC{slash}FB-Pad4)") (class "Default")
      (node (ref "U2") (pin "4") (pinfunction "NC/FB_4") (pintype "passive"))
    )
    (net (code "88") (name "unconnected-(U3-A1-Pad1)") (class "Default")
      (node (ref "U3") (pin "1") (pinfunction "A1_1") (pintype "bidirectional"))
    )
    (net (code "89") (name "unconnected-(U3-A2-Pad3)") (class "Default")
      (node (ref "U3") (pin "3") (pinfunction "A2_3") (pintype "bidirectional"))
    )
    (net (code "90") (name "unconnected-(U3-A7-Pad8)") (class "Default")
      (node (ref "U3") (pin "8") (pinfunction "A7_8") (pintype "bidirectional"))
    )
    (net (code "91") (name "unconnected-(U3-A8-Pad9)") (class "Default")
      (node (ref "U3") (pin "9") (pinfunction "A8_9") (pintype "bidirectional"))
    )
    (net (code "92") (name "unconnected-(U3-B1-Pad20)") (class "Default")
      (node (ref "U3") (pin "20") (pinfunction "B1_20") (pintype "bidirectional"))
    )
    (net (code "93") (name "unconnected-(U3-B2-Pad18)") (class "Default")
      (node (ref "U3") (pin "18") (pinfunction "B2_18") (pintype "bidirectional"))
    )
    (net (code "94") (name "unconnected-(U3-B7-Pad13)") (class "Default")
      (node (ref "U3") (pin "13") (pinfunction "B7_13") (pintype "bidirectional"))
    )
    (net (code "95") (name "unconnected-(U3-B8-Pad12)") (class "Default")
      (node (ref "U3") (pin "12") (pinfunction "B8_12") (pintype "bidirectional"))
    )
    (net (code "96") (name "unconnected-(U4-DVDD-Pad39)") (class "Default")
      (node (ref "U4") (pin "39") (pinfunction "DVDD_39") (pintype "bidirectional"))
    )
    (net (code "97") (name "unconnected-(U4-LOADMOD-Pad2)") (class "Default")
      (node (ref "U4") (pin "2") (pinfunction "LOADMOD_2") (pintype "bidirectional"))
    )
    (net (code "98") (name "unconnected-(U4-MISO-Pad29)") (class "Default")
      (node (ref "U4") (pin "29") (pinfunction "MISO_29") (pintype "bidirectional"))
    )
    (net (code "99") (name "unconnected-(U4-NC1-Pad20)") (class "Default")
      (node (ref "U4") (pin "20") (pinfunction "NC1_20") (pintype "bidirectional"))
    )
    (net (code "100") (name "unconnected-(U4-NC2-Pad21)") (class "Default")
      (node (ref "U4") (pin "21") (pinfunction "NC2_21") (pintype "bidirectional"))
    )
    (net (code "101") (name "unconnected-(U4-NC3-Pad22)") (class "Default")
      (node (ref "U4") (pin "22") (pinfunction "NC3_22") (pintype "bidirectional"))
    )
    (net (code "102") (name "unconnected-(U4-SCK-Pad30)") (class "Default")
      (node (ref "U4") (pin "30") (pinfunction "SCK_30") (pintype "bidirectional"))
    )
    (net (code "103") (name "unconnected-(X1-GND-Pad2)") (class "Default")
      (node (ref "X1") (pin "2") (pinfunction "GND_2") (pintype "passive"))
    )
  )
)
